# delay_module_easyeda.net
KiCad netlist of a schematic drawn in EasyEDA Pro
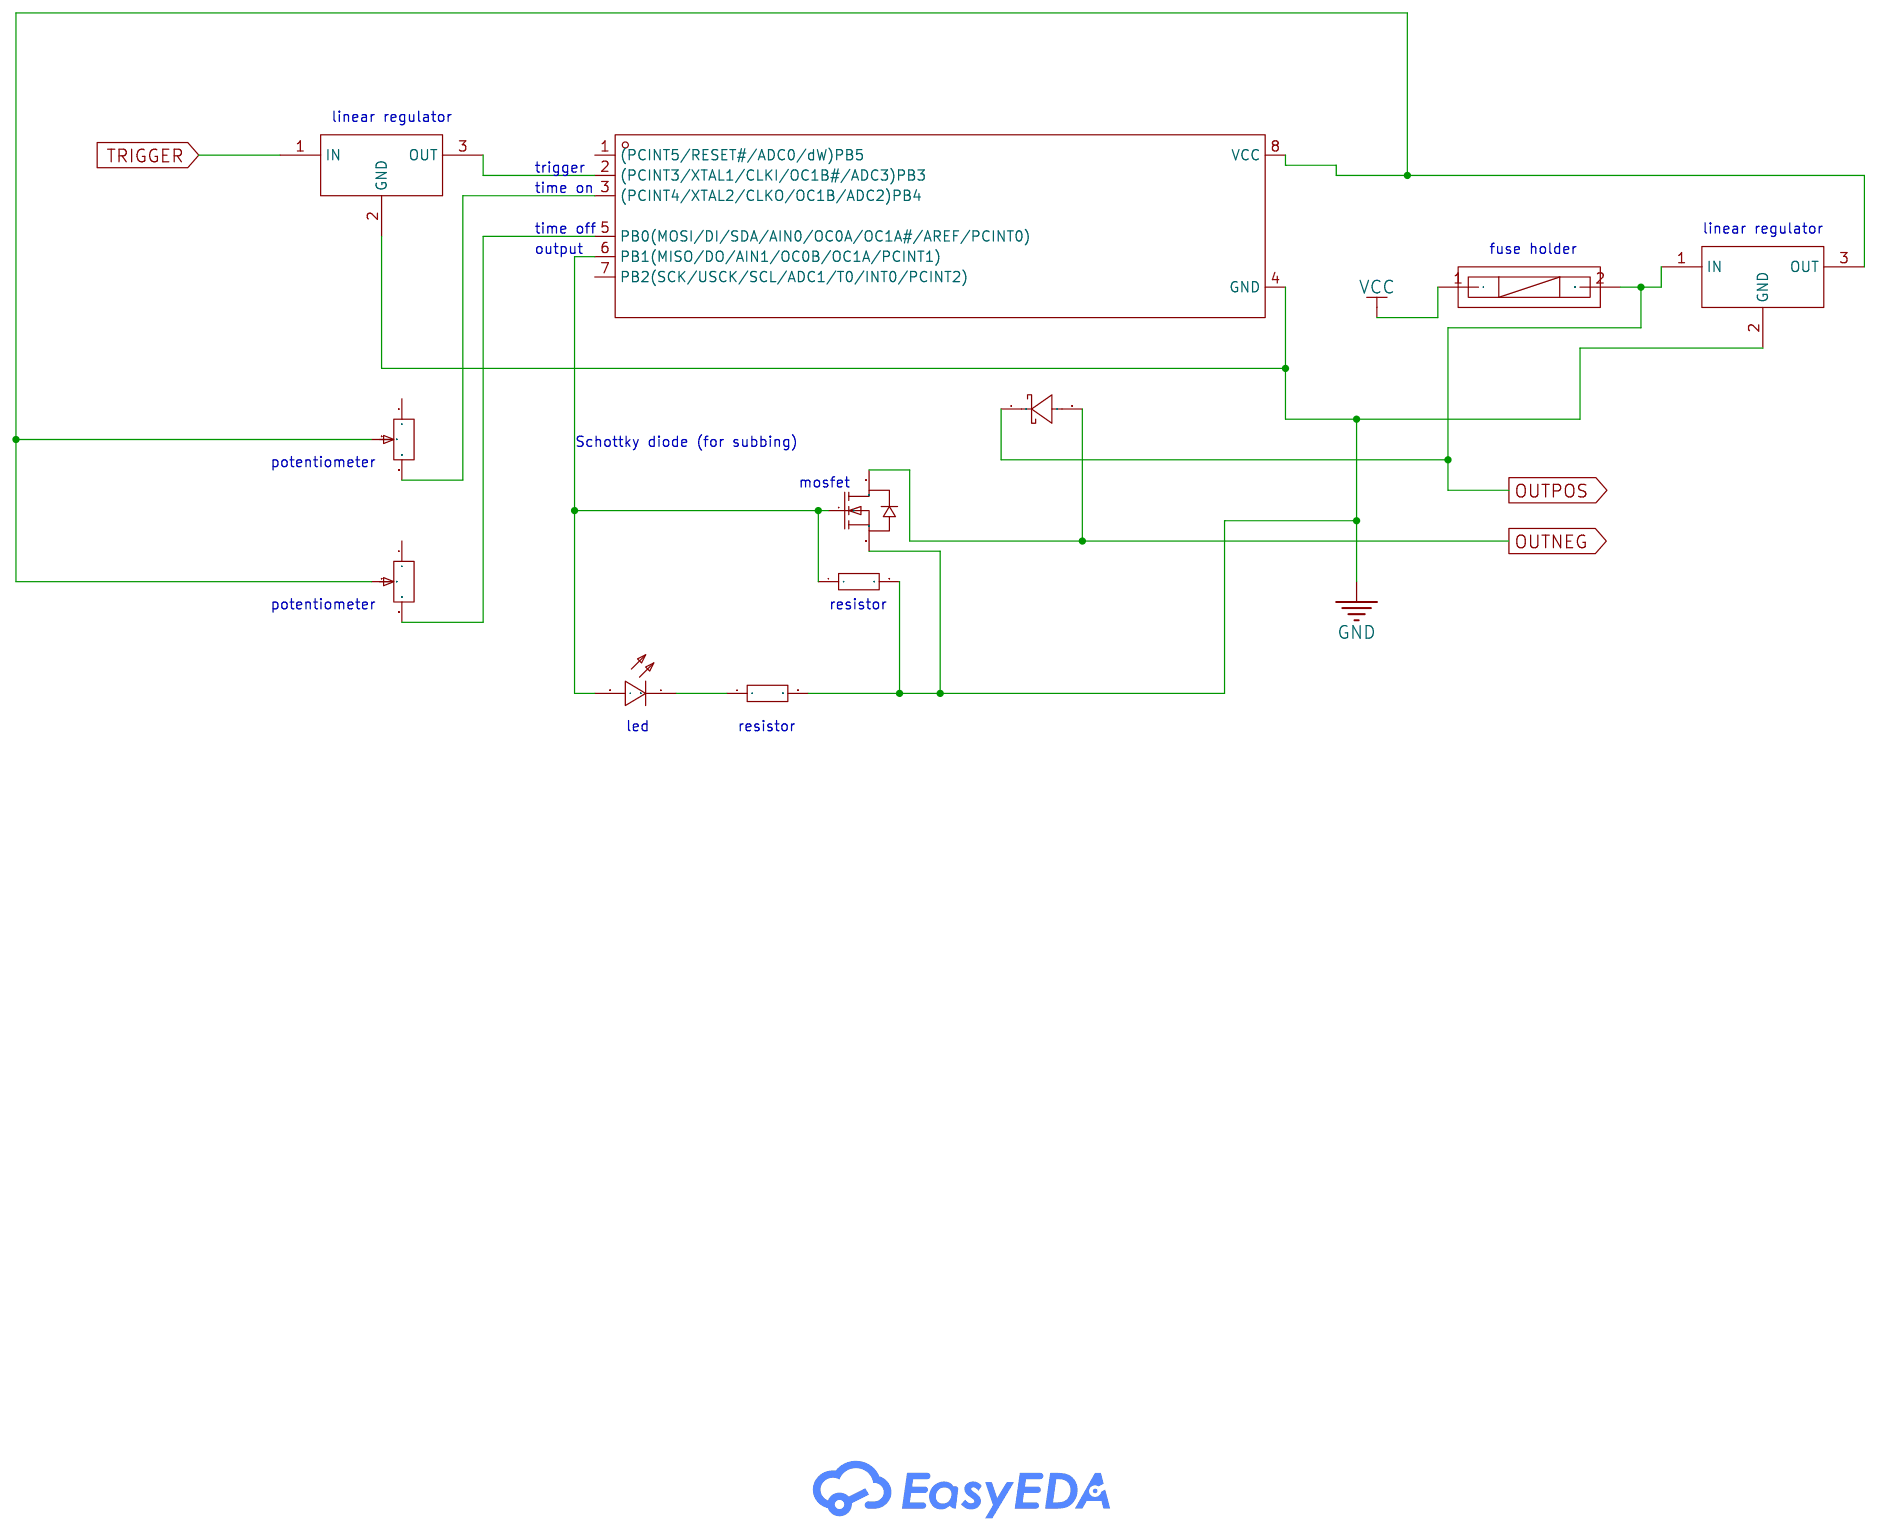
[diagram p0: schematic sheet]

(export (version "E")
  (design (tool "Eeschema 10.0.6"))
  (components
    (comp (ref "D1")
      (value "1N5819")
      (footprint "easyedapro:DO-41_BD2.4-L4.7-P8.70-D0.8-RD")
      (fields (field (name "Manufacturer") "luJing(鲁晶)"))
      (libsource (lib "easyedapro") (part "1N5819_C49318088"))
    )
    (comp (ref "F1")
      (value "5x20 BLX-A型 保险丝支架 XC-7")
      (footprint "easyedapro:FUSE-TH_L22.6-W9.0")
      (fields (field (name "Manufacturer") "xcfuse(旭程)"))
      (libsource (lib "easyedapro") (part "5x20 BLX-Atype Fuse holder XC-7"))
    )
    (comp (ref "IR1")
      (value "IR908-7C(E5)")
      (footprint "easyedapro:LED-TH_L4.5-W1.5-P2.54-RD")
      (fields (field (name "Manufacturer") "EVERLIGHT(亿光)"))
      (libsource (lib "easyedapro") (part "IR908-7C(E5)"))
    )
    (comp (ref "Q1")
      (value "FQP30N06L-VB")
      (footprint "easyedapro:TO-220AB-3_L10.3-W5.0-P2.54-L")
      (fields (field (name "Manufacturer") "VBsemi(微碧半导体)"))
      (libsource (lib "easyedapro") (part "FQP30N06L"))
    )
    (comp (ref "R1") (value "10K") (footprint "easyedapro:R0603") (libsource (lib "easyedapro") (part "Res")))
    (comp (ref "R2")
      (value "10kΩ")
      (footprint "easyedapro:RES-ADJ-TH_RK097111080J")
      (description "Resistance:10kΩ")
      (fields
        (field (name "Manufacturer Part") "RK097111080J")
        (field (name "Manufacturer") "ALPSALPINE(阿尔卑斯阿尔派)")
      )
      (libsource (lib "easyedapro") (part "RK097111080J"))
    )
    (comp (ref "R3")
      (value "10kΩ")
      (footprint "easyedapro:RES-ADJ-TH_RK097111080J")
      (description "Resistance:10kΩ")
      (fields
        (field (name "Manufacturer Part") "RK097111080J")
        (field (name "Manufacturer") "ALPSALPINE(阿尔卑斯阿尔派)")
      )
      (libsource (lib "easyedapro") (part "RK097111080J"))
    )
    (comp (ref "R4") (value "10K") (footprint "easyedapro:R0603") (libsource (lib "easyedapro") (part "Res")))
    (comp (ref "U1")
      (value "ATTINY85-20PU")
      (footprint "easyedapro:PDIP-8_L9.3-W6.4-P2.54-LS7.9-BL-1")
      (fields (field (name "Manufacturer") "MICROCHIP(美国微芯)"))
      (libsource (lib "easyedapro") (part "ATTINY85-20PU"))
    )
    (comp (ref "U2")
      (value "L7805CV")
      (footprint "easyedapro:TO-220-3_L10.0-W4.5-P2.54-L")
      (fields (field (name "Manufacturer") "GOODWORK(固得沃克)"))
      (libsource (lib "easyedapro") (part "L7805CV_C6430948"))
    )
    (comp (ref "U3")
      (value "L7805CV")
      (footprint "easyedapro:TO-220-3_L10.0-W4.5-P2.54-L")
      (fields (field (name "Manufacturer") "GOODWORK(固得沃克)"))
      (libsource (lib "easyedapro") (part "L7805CV_C6430948"))
    )
  )
  (nets
    (net (code "1") (name "GND") (class "Default")
      (node (ref "Q1") (pin "3") (pinfunction "S_3") (pintype "unspecified"))
      (node (ref "R1") (pin "2") (pinfunction "2_2") (pintype "input"))
      (node (ref "R4") (pin "2") (pinfunction "2_2") (pintype "input"))
      (node (ref "U1") (pin "4") (pinfunction "GND_4") (pintype "unspecified"))
      (node (ref "U2") (pin "2") (pinfunction "GND_2") (pintype "unspecified"))
      (node (ref "U3") (pin "2") (pinfunction "GND_2") (pintype "unspecified"))
    )
    (net (code "2") (name "Net-(IR1-A)") (class "Default")
      (node (ref "IR1") (pin "2") (pinfunction "A_2") (pintype "input"))
      (node (ref "Q1") (pin "1") (pinfunction "G_1") (pintype "unspecified"))
      (node (ref "R1") (pin "1") (pinfunction "1_1") (pintype "input"))
      (node (ref "U1") (pin "6") (pinfunction "PB1(MISO/DO/AIN1/OC0B/OC1A/PCINT1)_6") (pintype "unspecified"))
    )
    (net (code "3") (name "Net-(IR1-C)") (class "Default")
      (node (ref "IR1") (pin "1") (pinfunction "C_1") (pintype "input"))
      (node (ref "R4") (pin "1") (pinfunction "1_1") (pintype "input"))
    )
    (net (code "4") (name "Net-(U1-(PCINT3{slash}XTAL1{slash}CLKI{slash}OC1B#{slash}ADC3)PB3)") (class "Default")
      (node (ref "U1") (pin "2") (pinfunction "(PCINT3/XTAL1/CLKI/OC1B#/ADC3)PB3_2") (pintype "unspecified"))
      (node (ref "U2") (pin "3") (pinfunction "OUT_3") (pintype "unspecified"))
    )
    (net (code "5") (name "Net-(U1-(PCINT4{slash}XTAL2{slash}CLKO{slash}OC1B{slash}ADC2)PB4)") (class "Default")
      (node (ref "R2") (pin "3") (pinfunction "3_3") (pintype "input"))
      (node (ref "U1") (pin "3") (pinfunction "(PCINT4/XTAL2/CLKO/OC1B/ADC2)PB4_3") (pintype "unspecified"))
    )
    (net (code "6") (name "Net-(U1-PB0(MOSI{slash}DI{slash}SDA{slash}AIN0{slash}OC0A{slash}OC1A#{slash}AREF{slash}PCINT0))") (class "Default")
      (node (ref "R3") (pin "3") (pinfunction "3_3") (pintype "input"))
      (node (ref "U1") (pin "5") (pinfunction "PB0(MOSI/DI/SDA/AIN0/OC0A/OC1A#/AREF/PCINT0)_5") (pintype "unspecified"))
    )
    (net (code "7") (name "Net-(U1-VCC)") (class "Default")
      (node (ref "R2") (pin "2") (pinfunction "2_2") (pintype "input"))
      (node (ref "R3") (pin "2") (pinfunction "2_2") (pintype "input"))
      (node (ref "U1") (pin "8") (pinfunction "VCC_8") (pintype "unspecified"))
      (node (ref "U3") (pin "3") (pinfunction "OUT_3") (pintype "unspecified"))
    )
    (net (code "8") (name "OUTNEG") (class "Default")
      (node (ref "D1") (pin "2") (pinfunction "A_2") (pintype "unspecified"))
      (node (ref "Q1") (pin "2") (pinfunction "D_2") (pintype "unspecified"))
    )
    (net (code "9") (name "OUTPOS") (class "Default")
      (node (ref "D1") (pin "1") (pinfunction "C_1") (pintype "unspecified"))
      (node (ref "F1") (pin "2") (pinfunction "2_2") (pintype "unspecified"))
      (node (ref "U3") (pin "1") (pinfunction "IN_1") (pintype "unspecified"))
    )
    (net (code "10") (name "TRIGGER") (class "Default")
      (node (ref "U2") (pin "1") (pinfunction "IN_1") (pintype "unspecified"))
    )
    (net (code "11") (name "VCC") (class "Default")
      (node (ref "F1") (pin "1") (pinfunction "1_1") (pintype "unspecified"))
    )
    (net (code "12") (name "unconnected-(R2-Pad1)") (class "Default")
      (node (ref "R2") (pin "1") (pinfunction "1_1") (pintype "input"))
    )
    (net (code "13") (name "unconnected-(R3-Pad1)") (class "Default")
      (node (ref "R3") (pin "1") (pinfunction "1_1") (pintype "input"))
    )
    (net (code "14") (name "unconnected-(U1-(PCINT5{slash}RESET#{slash}ADC0{slash}dW)PB5-Pad1)") (class "Default")
      (node (ref "U1") (pin "1") (pinfunction "(PCINT5/RESET#/ADC0/dW)PB5_1") (pintype "unspecified"))
    )
    (net (code "15") (name "unconnected-(U1-PB2(SCK{slash}USCK{slash}SCL{slash}ADC1{slash}T0{slash}INT0{slash}PCINT2)-Pad7)") (class "Default")
      (node (ref "U1") (pin "7") (pinfunction "PB2(SCK/USCK/SCL/ADC1/T0/INT0/PCINT2)_7") (pintype "unspecified"))
    )
  )
)
